# Sheet1.net
KiCad netlist of a schematic drawn in Altium Designer
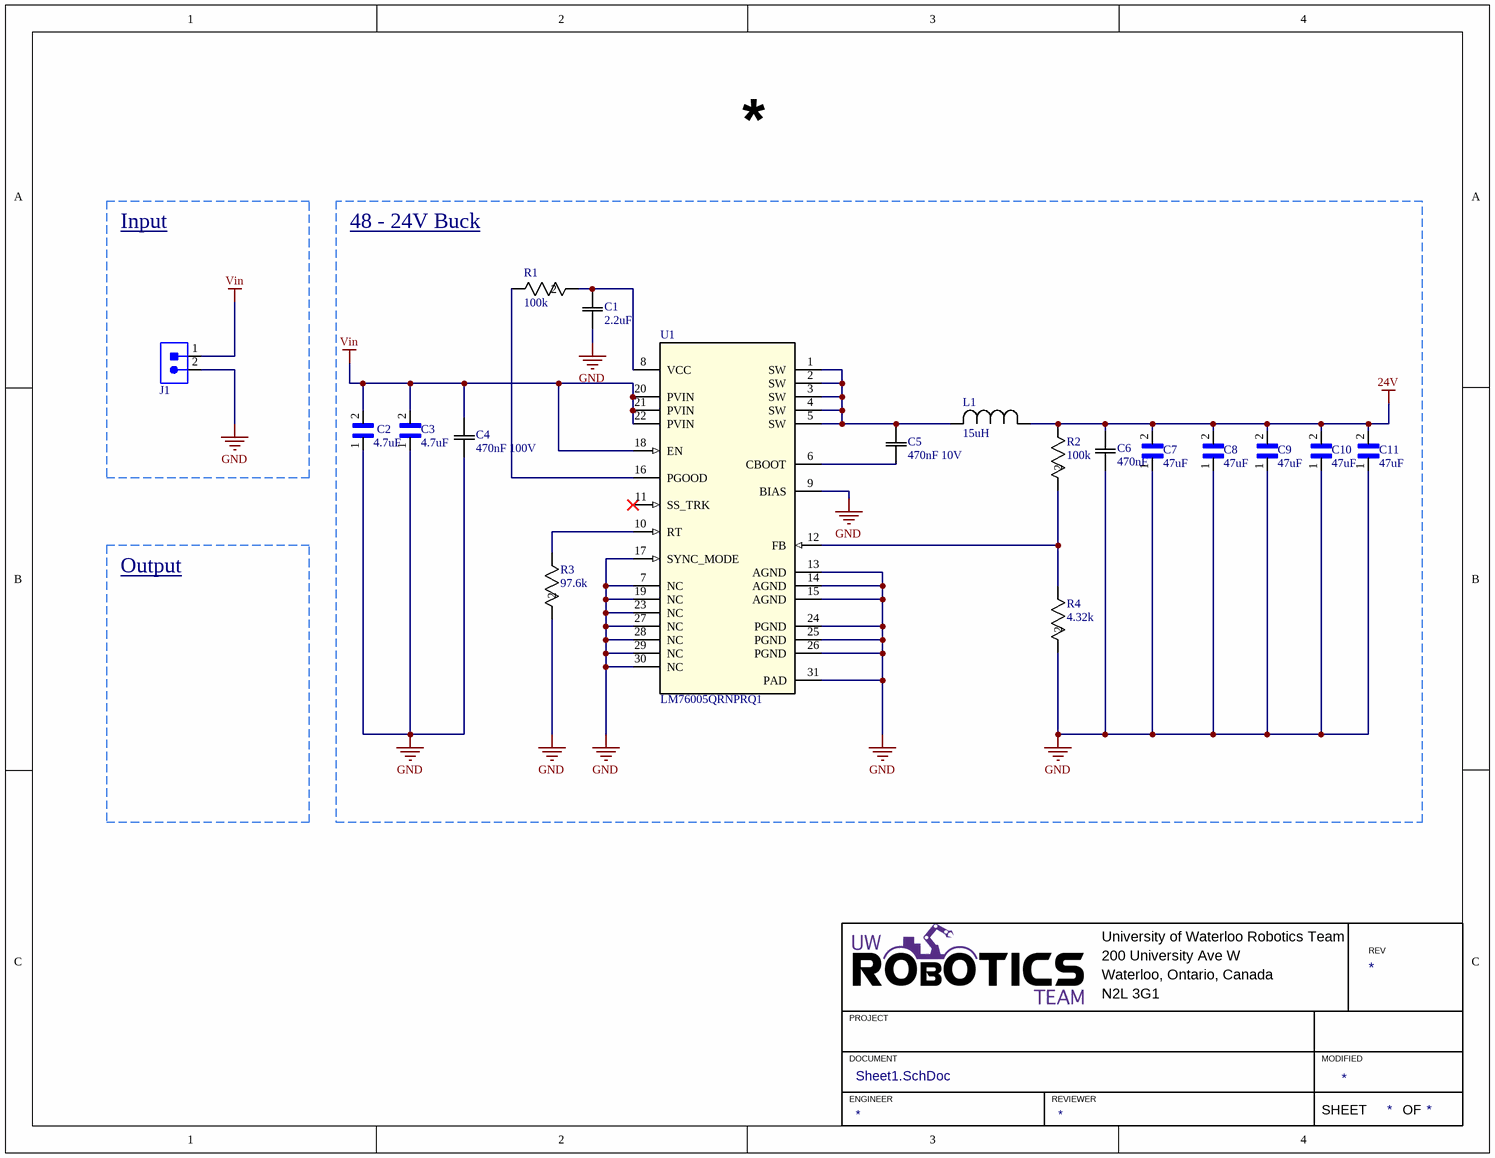
[diagram p0: Sheet1.SchDoc]

(export (version "E")
  (design (tool "Eeschema 10.0.6"))
  (components
    (comp (ref "C1")
      (value "2.2uF")
      (footprint "CAP_1608_TDK")
      (description "No Description Available")
      (libsource (lib "C1608X6S1C225K080AC") (part "C1608X6S1C225K080AC"))
    )
    (comp (ref "C2")
      (value "4.7uF")
      (footprint "CAPC3216X190N")
      (description "SMD Capacitor X7S(EIA) with Capacitance: 4.7uF Tol. 20%. Rated Voltage: 100Vdc")
      (fields (field (name "MP") "GRM31CC72A475ME11L"))
      (libsource (lib "GRM31CC72A475ME11L") (part "GRM31CC72A475ME11L"))
    )
    (comp (ref "C3")
      (value "4.7uF")
      (footprint "CAPC3216X190N")
      (description "SMD Capacitor X7S(EIA) with Capacitance: 4.7uF Tol. 20%. Rated Voltage: 100Vdc")
      (fields (field (name "MP") "GRM31CC72A475ME11L"))
      (libsource (lib "GRM31CC72A475ME11L") (part "GRM31CC72A475ME11L"))
    )
    (comp (ref "C4")
      (value "470nF 100V")
      (footprint "CAP_2012_TDK")
      (description "No Description Available")
      (libsource (lib "C2012X7S2A474K125AB") (part "C2012X7S2A474K125AB"))
    )
    (comp (ref "C5")
      (value "470nF 10V")
      (footprint "G-155_MUR")
      (description "No Description Available")
      (libsource (lib "GRM155R61A474KE15D") (part "GRM155R61A474KE15D"))
    )
    (comp (ref "C6")
      (value "470nF")
      (footprint "CAP_1608_TDK")
      (description "No Description Available")
      (libsource (lib "C1608X7R1H474K080AC") (part "C1608X7R1H474K080AC"))
    )
    (comp (ref "C7")
      (value "47uF")
      (footprint "CAPC6050X550N")
      (description "47 µF ±20% 50V Ceramic Capacitor X7R Stacked SMD, 2 J-Lead")
      (fields (field (name "MP") "CKG57NX7R1H476M500JH") (field (name "MF") "TDK Corporation"))
      (libsource (lib "CKG57NX7R1H476M500JH") (part "CKG57NX7R1H476M500JH"))
    )
    (comp (ref "C8")
      (value "47uF")
      (footprint "CAPC6050X550N")
      (description "47 ÂµF Â±20% 50V Ceramic Capacitor X7R Stacked SMD, 2 J-Lead")
      (fields (field (name "MP") "CKG57NX7R1H476M500JH") (field (name "MF") "TDK Corporation"))
      (libsource (lib "CKG57NX7R1H476M500JH") (part "CKG57NX7R1H476M500JH"))
    )
    (comp (ref "C9")
      (value "47uF")
      (footprint "CAPC6050X550N")
      (description "47 ÂµF Â±20% 50V Ceramic Capacitor X7R Stacked SMD, 2 J-Lead")
      (fields (field (name "MP") "CKG57NX7R1H476M500JH") (field (name "MF") "TDK Corporation"))
      (libsource (lib "CKG57NX7R1H476M500JH") (part "CKG57NX7R1H476M500JH"))
    )
    (comp (ref "C10")
      (value "47uF")
      (footprint "CAPC6050X550N")
      (description "47 ÂµF Â±20% 50V Ceramic Capacitor X7R Stacked SMD, 2 J-Lead")
      (fields (field (name "MP") "CKG57NX7R1H476M500JH") (field (name "MF") "TDK Corporation"))
      (libsource (lib "CKG57NX7R1H476M500JH") (part "CKG57NX7R1H476M500JH"))
    )
    (comp (ref "C11")
      (value "47uF")
      (footprint "CAPC6050X550N")
      (description "47 ÂµF Â±20% 50V Ceramic Capacitor X7R Stacked SMD, 2 J-Lead")
      (fields (field (name "MP") "CKG57NX7R1H476M500JH") (field (name "MF") "TDK Corporation"))
      (libsource (lib "CKG57NX7R1H476M500JH") (part "CKG57NX7R1H476M500JH"))
    )
    (comp (ref "J1")
      (value "CON_2POS_SCREW_TERM")
      (footprint "UWRT_Footprint_Library_2020:VP0265840000G")
      (description "PCB TERMINAL BLOCKS RISING CLAMP")
      (libsource (lib "UWRT_Schematic_Library_2020") (part "CON_2POS_SCREW_TERM_65A"))
    )
    (comp (ref "L1")
      (value "15uH")
      (footprint "IND_1890_2-WE-HCI_WRE")
      (description "No Description Available")
      (libsource (lib "74435571500") (part "74435571500"))
    )
    (comp (ref "R1")
      (value "100k")
      (footprint "RES_CRCW_0402_VIS")
      (description "No Description Available")
      (libsource (lib "CRCW0402100KFKED") (part "CRCW0402100KFKED"))
    )
    (comp (ref "R2")
      (value "100k")
      (footprint "RES_CRCW_0402_VIS")
      (description "No Description Available")
      (libsource (lib "CRCW0402100KFKED") (part "CRCW0402100KFKED"))
    )
    (comp (ref "R3")
      (value "97.6k")
      (footprint "RC0402N_VIS")
      (description "No Description Available")
      (libsource (lib "CRCW040297K6FKED") (part "CRCW040297K6FKED"))
    )
    (comp (ref "R4")
      (value "4.32k")
      (footprint "RC0603N_VIS")
      (description "No Description Available")
      (libsource (lib "CRCW06034K32FKEA") (part "CRCW06034K32FKEA"))
    )
    (comp (ref "U1")
      (value "LM76005QRNPRQ1")
      (footprint "RNP0030A")
      (description "No Description Available")
      (libsource (lib "LM76005QRNPRQ1") (part "LM76005QRNPRQ1"))
    )
  )
  (nets
    (net (code "1") (name "24V") (class "Default")
      (node (ref "C10") (pin "2") (pinfunction "2_2") (pintype "passive"))
      (node (ref "C11") (pin "2") (pinfunction "2_2") (pintype "passive"))
      (node (ref "C6") (pin "2") (pinfunction "2_2") (pintype "passive"))
      (node (ref "C7") (pin "2") (pinfunction "2_2") (pintype "passive"))
      (node (ref "C8") (pin "2") (pinfunction "2_2") (pintype "passive"))
      (node (ref "C9") (pin "2") (pinfunction "2_2") (pintype "passive"))
      (node (ref "L1") (pin "1") (pinfunction "1_1") (pintype "passive"))
      (node (ref "R2") (pin "1") (pinfunction "1_1") (pintype "passive"))
    )
    (net (code "2") (name "GND") (class "Default")
      (node (ref "C1") (pin "1") (pinfunction "1_1") (pintype "passive"))
      (node (ref "C10") (pin "1") (pinfunction "1_1") (pintype "passive"))
      (node (ref "C11") (pin "1") (pinfunction "1_1") (pintype "passive"))
      (node (ref "C2") (pin "1") (pinfunction "1_1") (pintype "passive"))
      (node (ref "C3") (pin "1") (pinfunction "1_1") (pintype "passive"))
      (node (ref "C4") (pin "1") (pinfunction "1_1") (pintype "passive"))
      (node (ref "C6") (pin "1") (pinfunction "1_1") (pintype "passive"))
      (node (ref "C7") (pin "1") (pinfunction "1_1") (pintype "passive"))
      (node (ref "C8") (pin "1") (pinfunction "1_1") (pintype "passive"))
      (node (ref "C9") (pin "1") (pinfunction "1_1") (pintype "passive"))
      (node (ref "J1") (pin "2") (pinfunction "2_2") (pintype "passive"))
      (node (ref "R3") (pin "2") (pinfunction "2_2") (pintype "passive"))
      (node (ref "R4") (pin "2") (pinfunction "2_2") (pintype "passive"))
      (node (ref "U1") (pin "13") (pinfunction "AGND_13") (pintype "power_in"))
      (node (ref "U1") (pin "14") (pinfunction "AGND_14") (pintype "power_in"))
      (node (ref "U1") (pin "15") (pinfunction "AGND_15") (pintype "power_in"))
      (node (ref "U1") (pin "17") (pinfunction "SYNC_MODE_17") (pintype "input"))
      (node (ref "U1") (pin "19") (pinfunction "NC_19") (pintype "passive"))
      (node (ref "U1") (pin "23") (pinfunction "NC_23") (pintype "passive"))
      (node (ref "U1") (pin "24") (pinfunction "PGND_24") (pintype "power_in"))
      (node (ref "U1") (pin "25") (pinfunction "PGND_25") (pintype "power_in"))
      (node (ref "U1") (pin "26") (pinfunction "PGND_26") (pintype "power_in"))
      (node (ref "U1") (pin "27") (pinfunction "NC_27") (pintype "passive"))
      (node (ref "U1") (pin "28") (pinfunction "NC_28") (pintype "passive"))
      (node (ref "U1") (pin "29") (pinfunction "NC_29") (pintype "passive"))
      (node (ref "U1") (pin "30") (pinfunction "NC_30") (pintype "passive"))
      (node (ref "U1") (pin "31") (pinfunction "PAD_31") (pintype "power_in"))
      (node (ref "U1") (pin "7") (pinfunction "NC_7") (pintype "passive"))
      (node (ref "U1") (pin "9") (pinfunction "BIAS_9") (pintype "passive"))
    )
    (net (code "3") (name "Net-(C5-Pad2)") (class "Default")
      (node (ref "C5") (pin "2") (pinfunction "2_2") (pintype "passive"))
      (node (ref "L1") (pin "2") (pinfunction "2_2") (pintype "passive"))
      (node (ref "U1") (pin "1") (pinfunction "SW_1") (pintype "power_in"))
      (node (ref "U1") (pin "2") (pinfunction "SW_2") (pintype "power_in"))
      (node (ref "U1") (pin "3") (pinfunction "SW_3") (pintype "power_in"))
      (node (ref "U1") (pin "4") (pinfunction "SW_4") (pintype "power_in"))
      (node (ref "U1") (pin "5") (pinfunction "SW_5") (pintype "power_in"))
    )
    (net (code "4") (name "Net-(U1-CBOOT)") (class "Default")
      (node (ref "C5") (pin "1") (pinfunction "1_1") (pintype "passive"))
      (node (ref "U1") (pin "6") (pinfunction "CBOOT_6") (pintype "power_in"))
    )
    (net (code "5") (name "Net-(U1-FB)") (class "Default")
      (node (ref "R2") (pin "2") (pinfunction "2_2") (pintype "passive"))
      (node (ref "R4") (pin "1") (pinfunction "1_1") (pintype "passive"))
      (node (ref "U1") (pin "12") (pinfunction "FB_12") (pintype "input"))
    )
    (net (code "6") (name "Net-(U1-PGOOD)") (class "Default")
      (node (ref "R1") (pin "1") (pinfunction "1_1") (pintype "passive"))
      (node (ref "U1") (pin "16") (pinfunction "PGOOD_16") (pintype "open_collector"))
    )
    (net (code "7") (name "Net-(U1-RT)") (class "Default")
      (node (ref "R3") (pin "1") (pinfunction "1_1") (pintype "passive"))
      (node (ref "U1") (pin "10") (pinfunction "RT_10") (pintype "input"))
    )
    (net (code "8") (name "Net-(U1-VCC)") (class "Default")
      (node (ref "C1") (pin "2") (pinfunction "2_2") (pintype "passive"))
      (node (ref "R1") (pin "2") (pinfunction "2_2") (pintype "passive"))
      (node (ref "U1") (pin "8") (pinfunction "VCC_8") (pintype "power_in"))
    )
    (net (code "9") (name "Vin") (class "Default")
      (node (ref "C2") (pin "2") (pinfunction "2_2") (pintype "passive"))
      (node (ref "C3") (pin "2") (pinfunction "2_2") (pintype "passive"))
      (node (ref "C4") (pin "2") (pinfunction "2_2") (pintype "passive"))
      (node (ref "J1") (pin "1") (pinfunction "1_1") (pintype "passive"))
      (node (ref "U1") (pin "18") (pinfunction "EN_18") (pintype "input"))
      (node (ref "U1") (pin "20") (pinfunction "PVIN_20") (pintype "power_in"))
      (node (ref "U1") (pin "21") (pinfunction "PVIN_21") (pintype "power_in"))
      (node (ref "U1") (pin "22") (pinfunction "PVIN_22") (pintype "power_in"))
    )
    (net (code "10") (name "unconnected-(U1-SS_TRK-Pad11)") (class "Default")
      (node (ref "U1") (pin "11") (pinfunction "SS_TRK_11") (pintype "input+no_connect"))
    )
  )
)
